# main_pcb.net
KiCad netlist of a schematic drawn in EAGLE
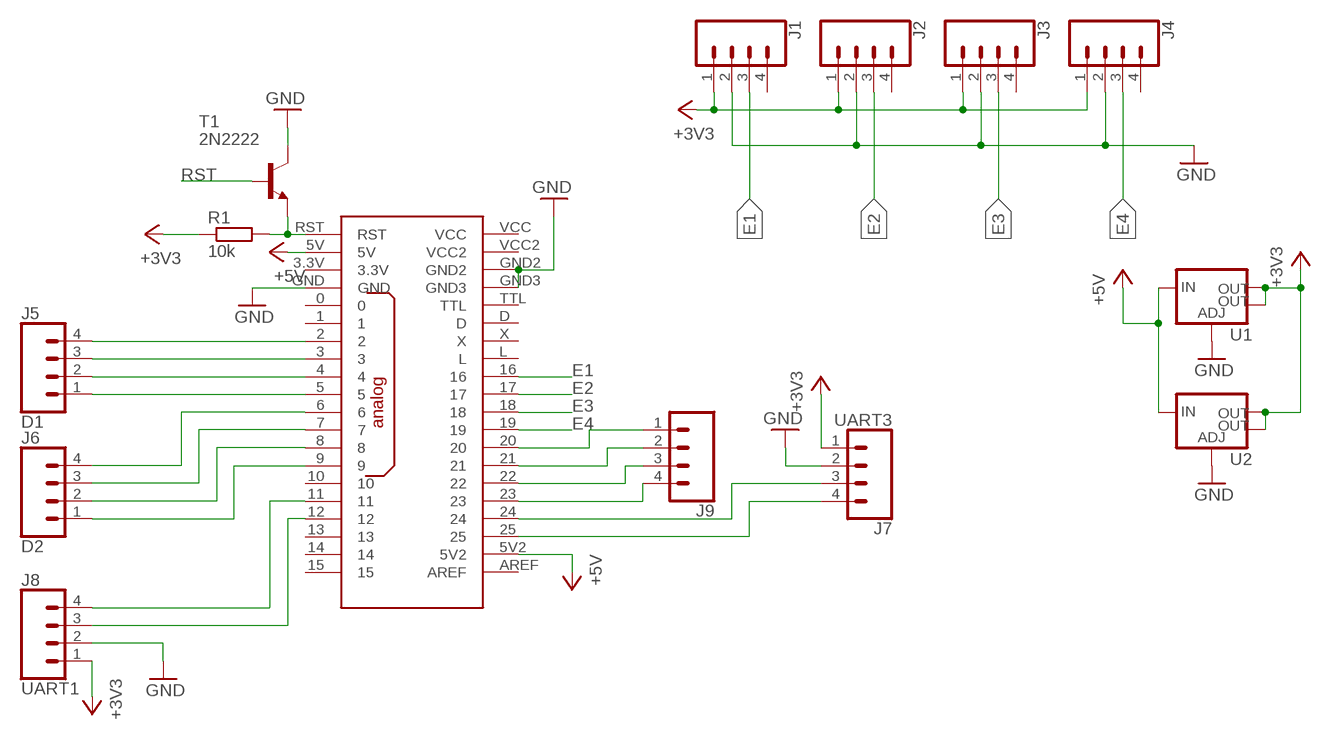
[diagram p0: schematic, sheet 1]

(export (version "E")
  (design (tool "Eeschema 10.0.6"))
  (components
    (comp (ref "J1")
      (value "CONN_04POLAR")
      (footprint "eagle-import:MOLEX-1X4")
      (libsource (lib "eagle-import") (part "CONN_04POLAR"))
    )
    (comp (ref "J2")
      (value "CONN_04POLAR")
      (footprint "eagle-import:MOLEX-1X4")
      (libsource (lib "eagle-import") (part "CONN_04POLAR"))
    )
    (comp (ref "J3")
      (value "CONN_04POLAR")
      (footprint "eagle-import:MOLEX-1X4")
      (libsource (lib "eagle-import") (part "CONN_04POLAR"))
    )
    (comp (ref "J4")
      (value "CONN_04POLAR")
      (footprint "eagle-import:MOLEX-1X4")
      (libsource (lib "eagle-import") (part "CONN_04POLAR"))
    )
    (comp (ref "J5")
      (value "D1")
      (footprint "eagle-import:MOLEX-1X4")
      (libsource (lib "eagle-import") (part "CONN_04POLAR"))
    )
    (comp (ref "J6")
      (value "D2")
      (footprint "eagle-import:MOLEX-1X4")
      (libsource (lib "eagle-import") (part "CONN_04POLAR"))
    )
    (comp (ref "J7")
      (value "UART3")
      (footprint "eagle-import:1X04")
      (libsource (lib "eagle-import") (part "CONN_04"))
    )
    (comp (ref "J8")
      (value "UART1")
      (footprint "eagle-import:1X04")
      (libsource (lib "eagle-import") (part "CONN_04"))
    )
    (comp (ref "J9")
      (value "CONN_04")
      (footprint "eagle-import:1X04")
      (libsource (lib "eagle-import") (part "CONN_04"))
    )
    (comp (ref "R1")
      (value "10k")
      (footprint "eagle-import:0204_7")
      (libsource (lib "eagle-import") (part "R-EU_0204/7"))
    )
    (comp (ref "T1")
      (value "2N2222")
      (footprint "eagle-import:TO18")
      (libsource (lib "eagle-import") (part "2N2222"))
    )
    (comp (ref "U$1")
      (value "OPENCM9.04")
      (footprint "eagle-import:OPENCM9.04")
      (libsource (lib "eagle-import") (part "OPENCM9.04"))
    )
    (comp (ref "U1")
      (value "V_REG_LM1117SOT223")
      (footprint "eagle-import:SOT223")
      (libsource (lib "eagle-import") (part "V_REG_LM1117SOT223"))
    )
    (comp (ref "U2")
      (value "V_REG_LM1117SOT223")
      (footprint "eagle-import:SOT223")
      (libsource (lib "eagle-import") (part "V_REG_LM1117SOT223"))
    )
  )
  (nets
    (net (code "1") (name "+3V3") (class "Default")
      (node (ref "J1") (pin "1") (pinfunction "1_1") (pintype "passive"))
      (node (ref "J2") (pin "1") (pinfunction "1_1") (pintype "passive"))
      (node (ref "J3") (pin "1") (pinfunction "1_1") (pintype "passive"))
      (node (ref "J4") (pin "1") (pinfunction "1_1") (pintype "passive"))
      (node (ref "J7") (pin "1") (pinfunction "1_1") (pintype "passive"))
      (node (ref "J8") (pin "1") (pinfunction "1_1") (pintype "passive"))
      (node (ref "R1") (pin "1") (pinfunction "1_1") (pintype "passive"))
      (node (ref "U1") (pin "2") (pinfunction "OUT_2") (pintype "output"))
      (node (ref "U1") (pin "4") (pinfunction "OUT_4") (pintype "output"))
      (node (ref "U2") (pin "2") (pinfunction "OUT_2") (pintype "output"))
      (node (ref "U2") (pin "4") (pinfunction "OUT_4") (pintype "output"))
    )
    (net (code "2") (name "+5V") (class "Default")
      (node (ref "U$1") (pin "5V") (pinfunction "5V_5V") (pintype "bidirectional"))
      (node (ref "U$1") (pin "5V2") (pinfunction "5V2_5V2") (pintype "bidirectional"))
      (node (ref "U1") (pin "3") (pinfunction "IN_3") (pintype "input"))
      (node (ref "U2") (pin "3") (pinfunction "IN_3") (pintype "input"))
    )
    (net (code "3") (name "/RST") (class "Default")
      (node (ref "T1") (pin "2") (pinfunction "B_2") (pintype "passive"))
    )
    (net (code "4") (name "E1") (class "Default")
      (node (ref "J1") (pin "3") (pinfunction "3_3") (pintype "passive"))
      (node (ref "U$1") (pin "16") (pinfunction "16_16") (pintype "bidirectional"))
    )
    (net (code "5") (name "E2") (class "Default")
      (node (ref "J2") (pin "3") (pinfunction "3_3") (pintype "passive"))
      (node (ref "U$1") (pin "17") (pinfunction "17_17") (pintype "bidirectional"))
    )
    (net (code "6") (name "E3") (class "Default")
      (node (ref "J3") (pin "3") (pinfunction "3_3") (pintype "passive"))
      (node (ref "U$1") (pin "18") (pinfunction "18_18") (pintype "bidirectional"))
    )
    (net (code "7") (name "E4") (class "Default")
      (node (ref "J4") (pin "3") (pinfunction "3_3") (pintype "passive"))
      (node (ref "U$1") (pin "19") (pinfunction "19_19") (pintype "bidirectional"))
    )
    (net (code "8") (name "GND") (class "Default")
      (node (ref "J1") (pin "2") (pinfunction "2_2") (pintype "passive"))
      (node (ref "J2") (pin "2") (pinfunction "2_2") (pintype "passive"))
      (node (ref "J3") (pin "2") (pinfunction "2_2") (pintype "passive"))
      (node (ref "J4") (pin "2") (pinfunction "2_2") (pintype "passive"))
      (node (ref "J7") (pin "2") (pinfunction "2_2") (pintype "passive"))
      (node (ref "J8") (pin "2") (pinfunction "2_2") (pintype "passive"))
      (node (ref "T1") (pin "3") (pinfunction "C_3") (pintype "passive"))
      (node (ref "U$1") (pin "GND") (pinfunction "GND_GND") (pintype "bidirectional"))
      (node (ref "U$1") (pin "GND2") (pinfunction "GND2_GND2") (pintype "bidirectional"))
      (node (ref "U$1") (pin "GND3") (pinfunction "GND3_GND3") (pintype "bidirectional"))
      (node (ref "U1") (pin "1") (pinfunction "ADJ_1") (pintype "input"))
      (node (ref "U2") (pin "1") (pinfunction "ADJ_1") (pintype "input"))
    )
    (net (code "9") (name "Net-(J5-Pad1)") (class "Default")
      (node (ref "J5") (pin "1") (pinfunction "1_1") (pintype "passive"))
      (node (ref "U$1") (pin "5") (pinfunction "5_5") (pintype "bidirectional"))
    )
    (net (code "10") (name "Net-(J5-Pad2)") (class "Default")
      (node (ref "J5") (pin "2") (pinfunction "2_2") (pintype "passive"))
      (node (ref "U$1") (pin "4") (pinfunction "4_4") (pintype "bidirectional"))
    )
    (net (code "11") (name "Net-(J5-Pad3)") (class "Default")
      (node (ref "J5") (pin "3") (pinfunction "3_3") (pintype "passive"))
      (node (ref "U$1") (pin "3") (pinfunction "3_3") (pintype "bidirectional"))
    )
    (net (code "12") (name "Net-(J5-Pad4)") (class "Default")
      (node (ref "J5") (pin "4") (pinfunction "4_4") (pintype "passive"))
      (node (ref "U$1") (pin "2") (pinfunction "2_2") (pintype "bidirectional"))
    )
    (net (code "13") (name "Net-(J6-Pad1)") (class "Default")
      (node (ref "J6") (pin "1") (pinfunction "1_1") (pintype "passive"))
      (node (ref "U$1") (pin "9") (pinfunction "9_9") (pintype "bidirectional"))
    )
    (net (code "14") (name "Net-(J6-Pad2)") (class "Default")
      (node (ref "J6") (pin "2") (pinfunction "2_2") (pintype "passive"))
      (node (ref "U$1") (pin "8") (pinfunction "8_8") (pintype "bidirectional"))
    )
    (net (code "15") (name "Net-(J6-Pad3)") (class "Default")
      (node (ref "J6") (pin "3") (pinfunction "3_3") (pintype "passive"))
      (node (ref "U$1") (pin "7") (pinfunction "7_7") (pintype "bidirectional"))
    )
    (net (code "16") (name "Net-(J6-Pad4)") (class "Default")
      (node (ref "J6") (pin "4") (pinfunction "4_4") (pintype "passive"))
      (node (ref "U$1") (pin "6") (pinfunction "6_6") (pintype "bidirectional"))
    )
    (net (code "17") (name "Net-(J7-Pad3)") (class "Default")
      (node (ref "J7") (pin "3") (pinfunction "3_3") (pintype "passive"))
      (node (ref "U$1") (pin "24") (pinfunction "24_24") (pintype "bidirectional"))
    )
    (net (code "18") (name "Net-(J7-Pad4)") (class "Default")
      (node (ref "J7") (pin "4") (pinfunction "4_4") (pintype "passive"))
      (node (ref "U$1") (pin "25") (pinfunction "25_25") (pintype "bidirectional"))
    )
    (net (code "19") (name "Net-(J8-Pad3)") (class "Default")
      (node (ref "J8") (pin "3") (pinfunction "3_3") (pintype "passive"))
      (node (ref "U$1") (pin "12") (pinfunction "12_12") (pintype "bidirectional"))
    )
    (net (code "20") (name "Net-(J8-Pad4)") (class "Default")
      (node (ref "J8") (pin "4") (pinfunction "4_4") (pintype "passive"))
      (node (ref "U$1") (pin "11") (pinfunction "11_11") (pintype "bidirectional"))
    )
    (net (code "21") (name "Net-(J9-Pad1)") (class "Default")
      (node (ref "J9") (pin "1") (pinfunction "1_1") (pintype "passive"))
      (node (ref "U$1") (pin "20") (pinfunction "20_20") (pintype "bidirectional"))
    )
    (net (code "22") (name "Net-(J9-Pad2)") (class "Default")
      (node (ref "J9") (pin "2") (pinfunction "2_2") (pintype "passive"))
      (node (ref "U$1") (pin "21") (pinfunction "21_21") (pintype "bidirectional"))
    )
    (net (code "23") (name "Net-(J9-Pad3)") (class "Default")
      (node (ref "J9") (pin "3") (pinfunction "3_3") (pintype "passive"))
      (node (ref "U$1") (pin "22") (pinfunction "22_22") (pintype "bidirectional"))
    )
    (net (code "24") (name "Net-(J9-Pad4)") (class "Default")
      (node (ref "J9") (pin "4") (pinfunction "4_4") (pintype "passive"))
      (node (ref "U$1") (pin "23") (pinfunction "23_23") (pintype "bidirectional"))
    )
    (net (code "25") (name "Net-(T1-E)") (class "Default")
      (node (ref "R1") (pin "2") (pinfunction "2_2") (pintype "passive"))
      (node (ref "T1") (pin "1") (pinfunction "E_1") (pintype "passive"))
      (node (ref "U$1") (pin "RST") (pinfunction "RST_RST") (pintype "bidirectional"))
    )
    (net (code "26") (name "unconnected-(J1-Pad4)") (class "Default")
      (node (ref "J1") (pin "4") (pinfunction "4_4") (pintype "passive"))
    )
    (net (code "27") (name "unconnected-(J2-Pad4)") (class "Default")
      (node (ref "J2") (pin "4") (pinfunction "4_4") (pintype "passive"))
    )
    (net (code "28") (name "unconnected-(J3-Pad4)") (class "Default")
      (node (ref "J3") (pin "4") (pinfunction "4_4") (pintype "passive"))
    )
    (net (code "29") (name "unconnected-(J4-Pad4)") (class "Default")
      (node (ref "J4") (pin "4") (pinfunction "4_4") (pintype "passive"))
    )
    (net (code "30") (name "unconnected-(U$1-Pad0)") (class "Default")
      (node (ref "U$1") (pin "0") (pinfunction "0_0") (pintype "bidirectional"))
    )
    (net (code "31") (name "unconnected-(U$1-Pad1)") (class "Default")
      (node (ref "U$1") (pin "1") (pinfunction "1_1") (pintype "bidirectional"))
    )
    (net (code "32") (name "unconnected-(U$1-Pad3.3V)") (class "Default")
      (node (ref "U$1") (pin "3.3V") (pinfunction "3.3V_3.3V") (pintype "bidirectional"))
    )
    (net (code "33") (name "unconnected-(U$1-Pad10)") (class "Default")
      (node (ref "U$1") (pin "10") (pinfunction "10_10") (pintype "bidirectional"))
    )
    (net (code "34") (name "unconnected-(U$1-Pad13)") (class "Default")
      (node (ref "U$1") (pin "13") (pinfunction "13_13") (pintype "bidirectional"))
    )
    (net (code "35") (name "unconnected-(U$1-Pad14)") (class "Default")
      (node (ref "U$1") (pin "14") (pinfunction "14_14") (pintype "bidirectional"))
    )
    (net (code "36") (name "unconnected-(U$1-Pad15)") (class "Default")
      (node (ref "U$1") (pin "15") (pinfunction "15_15") (pintype "bidirectional"))
    )
    (net (code "37") (name "unconnected-(U$1-PadAREF)") (class "Default")
      (node (ref "U$1") (pin "AREF") (pinfunction "AREF_AREF") (pintype "bidirectional"))
    )
    (net (code "38") (name "unconnected-(U$1-PadD)") (class "Default")
      (node (ref "U$1") (pin "D") (pinfunction "D_D") (pintype "bidirectional"))
    )
    (net (code "39") (name "unconnected-(U$1-PadL)") (class "Default")
      (node (ref "U$1") (pin "L") (pinfunction "L_L") (pintype "bidirectional"))
    )
    (net (code "40") (name "unconnected-(U$1-PadTTL)") (class "Default")
      (node (ref "U$1") (pin "TTL") (pinfunction "TTL_TTL") (pintype "bidirectional"))
    )
    (net (code "41") (name "unconnected-(U$1-PadVCC)") (class "Default")
      (node (ref "U$1") (pin "VCC") (pinfunction "VCC_VCC") (pintype "bidirectional"))
    )
    (net (code "42") (name "unconnected-(U$1-PadVCC2)") (class "Default")
      (node (ref "U$1") (pin "VCC2") (pinfunction "VCC2_VCC2") (pintype "bidirectional"))
    )
    (net (code "43") (name "unconnected-(U$1-PadX)") (class "Default")
      (node (ref "U$1") (pin "X") (pinfunction "X_X") (pintype "bidirectional"))
    )
  )
)
